# Microcontroller.net
KiCad netlist of a schematic drawn in Altium Designer
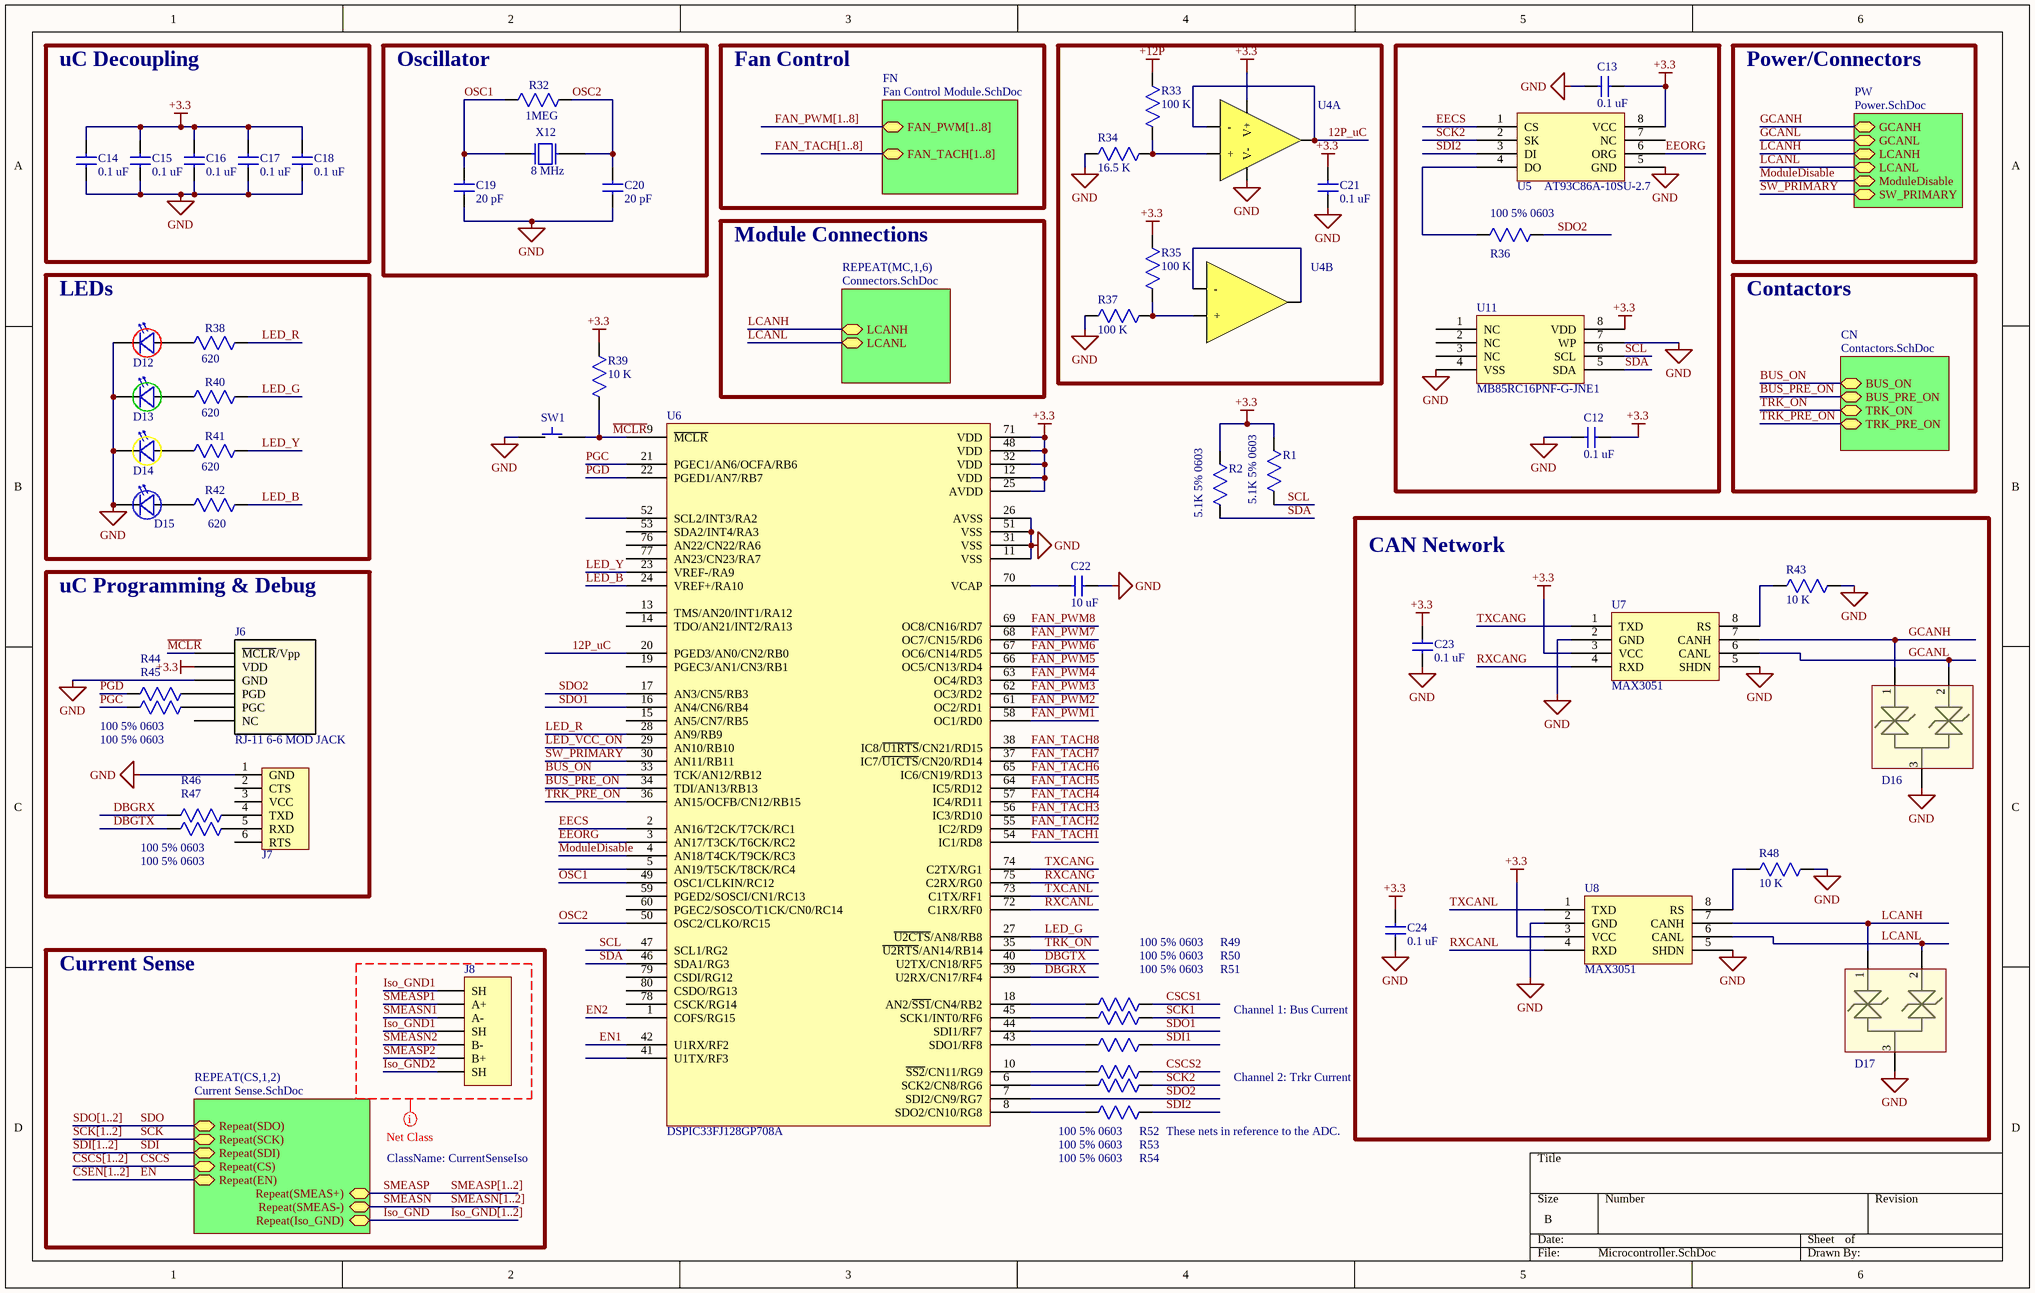
[diagram p0: Microcontroller.SchDoc]

(export (version "E")
  (design (tool "Eeschema 10.0.6"))
  (components
    (comp (ref "C12")
      (value "0.1 uF")
      (footprint "0603_cap")
      (description "CAP CERM 0603")
      (fields (field (name "Comment") "CAP 0603"))
      (libsource (lib "Nutz") (part "C_0603"))
    )
    (comp (ref "C13")
      (value "0.1 uF")
      (footprint "0603_cap")
      (description "CAP CERM 0603")
      (fields (field (name "Comment") "CAP 0603"))
      (libsource (lib "Nutz") (part "C_0603"))
    )
    (comp (ref "C14")
      (value "0.1 uF")
      (footprint "0603_cap")
      (description "CAP CERM 0603")
      (fields (field (name "Comment") "CAP 0603"))
      (libsource (lib "Nutz") (part "C_0603"))
    )
    (comp (ref "C15")
      (value "0.1 uF")
      (footprint "0603_cap")
      (description "CAP CERM 0603")
      (fields (field (name "Comment") "CAP 0603"))
      (libsource (lib "Nutz") (part "C_0603"))
    )
    (comp (ref "C16")
      (value "0.1 uF")
      (footprint "0603_cap")
      (description "CAP CERM 0603")
      (fields (field (name "Comment") "CAP 0603"))
      (libsource (lib "Nutz") (part "C_0603"))
    )
    (comp (ref "C17")
      (value "0.1 uF")
      (footprint "0603_cap")
      (description "CAP CERM 0603")
      (fields (field (name "Comment") "CAP 0603"))
      (libsource (lib "Nutz") (part "C_0603"))
    )
    (comp (ref "C18")
      (value "0.1 uF")
      (footprint "0603_cap")
      (description "CAP CERM 0603")
      (fields (field (name "Comment") "CAP 0603"))
      (libsource (lib "Nutz") (part "C_0603"))
    )
    (comp (ref "C19")
      (value "20 pF")
      (footprint "0805_Capacitor")
      (description "CAP CERM 20PF 5% 100V NP0 0805")
      (fields
        (field (name "MANUFACTURER") "AVX")
        (field (name "Comment") "CAP 20PF")
        (field (name "SVP CREATOR") "Jonathan Nutzmann")
      )
      (libsource (lib "c3_SchLib") (part "C_0805_20PF_100V_5%"))
    )
    (comp (ref "C20")
      (value "20 pF")
      (footprint "0805_Capacitor")
      (description "CAP CERM 20PF 5% 100V NP0 0805")
      (fields
        (field (name "MANUFACTURER") "AVX")
        (field (name "Comment") "CAP 20PF")
        (field (name "SVP CREATOR") "Jonathan Nutzmann")
      )
      (libsource (lib "c3_SchLib") (part "C_0805_20PF_100V_5%"))
    )
    (comp (ref "C21")
      (value "0.1 uF")
      (footprint "0603_cap")
      (description "CAP CERM 0603")
      (fields (field (name "Comment") "CAP 0603"))
      (libsource (lib "Nutz") (part "C_0603"))
    )
    (comp (ref "C22")
      (value "10 uF")
      (footprint "0805_Capacitor")
      (description "CAP CERM 10 uF")
      (fields (field (name "Comment") "CAP 10 uF"))
      (libsource (lib "c3_SchLib") (part "C_0805_10uF"))
    )
    (comp (ref "C23")
      (value "0.1 uF")
      (footprint "0603_cap")
      (description "CAP CERM 0603")
      (fields (field (name "Comment") "CAP 0603"))
      (libsource (lib "Nutz") (part "C_0603"))
    )
    (comp (ref "C24")
      (value "0.1 uF")
      (footprint "0603_cap")
      (description "CAP CERM 0603")
      (fields (field (name "Comment") "CAP 0603"))
      (libsource (lib "Nutz") (part "C_0603"))
    )
    (comp (ref "D12")
      (value "D_LED_0805_RED")
      (footprint "0805P_RED")
      (description "LED CHIPLED 645NM RED DIFF 0805")
      (fields (field (name "SVP CREATOR") "Jonathan Nutzmann"))
      (libsource (lib "c3_SchLib") (part "D_LED_0805_RED"))
    )
    (comp (ref "D13")
      (value "D_LED_0805_GREEN")
      (footprint "0805P_Green")
      (description "LED CHIPLED 570NM GREEN 0805 SMD")
      (fields
        (field (name "MANUFACTURER") "Osram Opto Semiconductors Inc")
        (field (name "SVP CREATOR") "Nate Bolyard")
        (field (name "SVP REVIEWER 1") "Trevtron")
      )
      (libsource (lib "c3_SchLib") (part "D_LED_0805_GREEN"))
    )
    (comp (ref "D14")
      (value "D_LED_0805_YELLOW")
      (footprint "0805P_YELLOW")
      (description "LED 595NM AMBER DIFF SMD 0805")
      (fields (field (name "SVP CREATOR") "Jonathan Nutzmann"))
      (libsource (lib "c3_SchLib") (part "D_LED_0805_YELLOW"))
    )
    (comp (ref "D15")
      (value "D_LED_0805_BLUE")
      (footprint "0805_BLUE")
      (description "LED 2X1.2MM 470NM BL WTR CLR SMD")
      (fields (field (name "SVP CREATOR") "Jonathan Nutzmann"))
      (libsource (lib "c3_SchLib") (part "D_LED_0805_BLUE"))
    )
    (comp (ref "D16")
      (value "CAN TVS")
      (footprint "SOT-23")
      (description "IC CAN BUS PROTECTOR DUAL SOT23")
      (fields (field (name "MANUFACTURER") "ON Semiconductor") (field (name "SVP CREATOR") "Thomas Daede"))
      (libsource (lib "c3_SchLib") (part "D_NUP2105"))
    )
    (comp (ref "D17")
      (value "CAN TVS")
      (footprint "SOT-23")
      (description "IC CAN BUS PROTECTOR DUAL SOT23")
      (fields (field (name "MANUFACTURER") "ON Semiconductor") (field (name "SVP CREATOR") "Thomas Daede"))
      (libsource (lib "c3_SchLib") (part "D_NUP2105"))
    )
    (comp (ref "J6")
      (value "RJ-11 6-6 MOD JACK")
      (footprint "SS-6466-NF")
      (description "SCS RJ-11 Jack")
      (libsource (lib "c3_SchLib") (part "J_ICD PROG"))
    )
    (comp (ref "J7")
      (value "IDC Connector")
      (footprint "6PIN_1_.100IN")
      (description "FTDI Cable VCC I/O")
      (fields (field (name "SVP CREATOR") "Jonathan Nutzmann"))
      (libsource (lib "c3_SchLib") (part "JP_FTDI_USB"))
    )
    (comp (ref "J8")
      (value "J_SATA_0471554001")
      (footprint "SATA_67800-8005")
      (description "CONN SATA HDR 7POS PCB VERT")
      (fields (field (name "MANUFACTURER") "Molex"))
      (libsource (lib "c3_SchLib") (part "J_SATA_0471554001"))
    )
    (comp (ref "R1")
      (value "5.1K 5% 0603")
      (footprint "0603_res")
      (description "RES 0603")
      (libsource (lib "Nutz") (part "R_0603"))
    )
    (comp (ref "R2")
      (value "5.1K 5% 0603")
      (footprint "0603_res")
      (description "RES 0603")
      (libsource (lib "Nutz") (part "R_0603"))
    )
    (comp (ref "R32")
      (value "1MEG")
      (footprint "0805_Resistor")
      (description "RES 1MEG OHM 1/8W 1% 0805 SMD")
      (fields (field (name "Comment") "R_0805_1MEG_1%") (field (name "SVP CREATOR") "Brett Paulsen"))
      (libsource (lib "c3_SchLib") (part "R_0805_1MEG_1%"))
    )
    (comp (ref "R33")
      (value "100 K")
      (footprint "0603_res")
      (description "RES 0603")
      (libsource (lib "Nutz") (part "R_0603"))
    )
    (comp (ref "R34")
      (value "16.5 K")
      (footprint "0603_res")
      (description "RES 0603")
      (libsource (lib "Nutz") (part "R_0603"))
    )
    (comp (ref "R35")
      (value "100 K")
      (footprint "0603_res")
      (description "RES 0603")
      (libsource (lib "Nutz") (part "R_0603"))
    )
    (comp (ref "R36")
      (value "100 5% 0603")
      (footprint "0603_res")
      (description "RES 0603")
      (libsource (lib "Nutz") (part "R_0603"))
    )
    (comp (ref "R37")
      (value "100 K")
      (footprint "0603_res")
      (description "RES 0603")
      (libsource (lib "Nutz") (part "R_0603"))
    )
    (comp (ref "R38")
      (value "620")
      (footprint "0805_Resistor")
      (description "RES 620 OHM 1/8W 1% 0805 SMD")
      (fields (field (name "Comment") "R_0805_620_1%") (field (name "SVP CREATOR") "Jonathan Nutzmann"))
      (libsource (lib "c3_SchLib") (part "R_0805_620_1%"))
    )
    (comp (ref "R39")
      (value "10 K")
      (footprint "0603_res")
      (description "RES 0603")
      (libsource (lib "Nutz") (part "R_0603"))
    )
    (comp (ref "R40")
      (value "620")
      (footprint "0805_Resistor")
      (description "RES 620 OHM 1/8W 1% 0805 SMD")
      (fields (field (name "Comment") "R_0805_620_1%") (field (name "SVP CREATOR") "Jonathan Nutzmann"))
      (libsource (lib "c3_SchLib") (part "R_0805_620_1%"))
    )
    (comp (ref "R41")
      (value "620")
      (footprint "0805_Resistor")
      (description "RES 620 OHM 1/8W 1% 0805 SMD")
      (fields (field (name "Comment") "R_0805_620_1%") (field (name "SVP CREATOR") "Jonathan Nutzmann"))
      (libsource (lib "c3_SchLib") (part "R_0805_620_1%"))
    )
    (comp (ref "R42")
      (value "620")
      (footprint "0805_Resistor")
      (description "RES 620 OHM 1/8W 1% 0805 SMD")
      (fields (field (name "Comment") "R_0805_620_1%") (field (name "SVP CREATOR") "Jonathan Nutzmann"))
      (libsource (lib "c3_SchLib") (part "R_0805_620_1%"))
    )
    (comp (ref "R43")
      (value "10 K")
      (footprint "0603_res")
      (description "RES 0603")
      (libsource (lib "Nutz") (part "R_0603"))
    )
    (comp (ref "R44")
      (value "100 5% 0603")
      (footprint "0603_res")
      (description "RES 0603")
      (libsource (lib "Nutz") (part "R_0603"))
    )
    (comp (ref "R45")
      (value "100 5% 0603")
      (footprint "0603_res")
      (description "RES 0603")
      (libsource (lib "Nutz") (part "R_0603"))
    )
    (comp (ref "R46")
      (value "100 5% 0603")
      (footprint "0603_res")
      (description "RES 0603")
      (libsource (lib "Nutz") (part "R_0603"))
    )
    (comp (ref "R47")
      (value "100 5% 0603")
      (footprint "0603_res")
      (description "RES 0603")
      (libsource (lib "Nutz") (part "R_0603"))
    )
    (comp (ref "R48")
      (value "10 K")
      (footprint "0603_res")
      (description "RES 0603")
      (libsource (lib "Nutz") (part "R_0603"))
    )
    (comp (ref "R49")
      (value "100 5% 0603")
      (footprint "0603_res")
      (description "RES 0603")
      (libsource (lib "Nutz") (part "R_0603"))
    )
    (comp (ref "R50")
      (value "100 5% 0603")
      (footprint "0603_res")
      (description "RES 0603")
      (libsource (lib "Nutz") (part "R_0603"))
    )
    (comp (ref "R51")
      (value "100 5% 0603")
      (footprint "0603_res")
      (description "RES 0603")
      (libsource (lib "Nutz") (part "R_0603"))
    )
    (comp (ref "R52")
      (value "100 5% 0603")
      (footprint "0603_res")
      (description "RES 0603")
      (libsource (lib "Nutz") (part "R_0603"))
    )
    (comp (ref "R53")
      (value "100 5% 0603")
      (footprint "0603_res")
      (description "RES 0603")
      (libsource (lib "Nutz") (part "R_0603"))
    )
    (comp (ref "R54")
      (value "100 5% 0603")
      (footprint "0603_res")
      (description "RES 0603")
      (libsource (lib "Nutz") (part "R_0603"))
    )
    (comp (ref "SW1")
      (value "SW_TACT_SWITCH_6x6")
      (footprint "TACT_SWITCH_6x6")
      (description "SWITCH TACT 6MM BLACK 160GF")
      (fields (field (name "MANUFACTURER") "Tyco Electronics") (field (name "SVP CREATOR") "Nate Bolyard"))
      (libsource (lib "c3_SchLib") (part "SW_TACT_SWITCH_6x6"))
    )
    (comp (ref "U4")
      (value "IC OP AMP")
      (footprint "SOIC127P600X175-8N")
      (description "IC OPAMP 1UA 1.4V DUAL R-R 8SOIC")
      (fields (field (name "MANUFACTURER") "Microchip") (field (name "SVP CREATOR") "Jonathan Nutzmann"))
      (libsource (lib "c3_SchLib") (part "U_MCP6042T-I/SN"))
    )
    (comp (ref "U5")
      (value "AT93C86A-10SU-2.7")
      (footprint "SOIC127P600X175-8N")
      (description "IC EEPROM 16KBIT 2MHZ 8SOIC")
      (fields (field (name "MANUFACTURER") "Atmel") (field (name "MANUFACTURER PN") "AT93C86A-10SU-2.7"))
      (libsource (lib "c3_SchLib") (part "U_AT93C86A-10SU-2.7"))
    )
    (comp (ref "U6")
      (value "DSPIC33FJ128GP708A")
      (footprint "dspic33-tqfp80")
      (description "IC DSPIC MCU/DSP 128K 80-TQFP")
      (fields (field (name "MANUFACTURER") "Microchip") (field (name "SVP CREATOR") "Jonathan Nutzmann"))
      (libsource (lib "c3_SchLib") (part "U_DSPIC33FJ128GP708A"))
    )
    (comp (ref "U7")
      (value "MAX3051")
      (footprint "SOIC127P600X175-8N")
      (description "IC TXRX CAN 1MBPS 8-SOIC 3.3V")
      (fields
        (field (name "MANUFACTURER") "Maxim")
        (field (name "Comment") "U_MAX3051")
        (field (name "SVP CREATOR") "Jonathan Nutzmann")
      )
      (libsource (lib "c3_SchLib") (part "U_MAX3051"))
    )
    (comp (ref "U8")
      (value "MAX3051")
      (footprint "SOIC127P600X175-8N")
      (description "IC TXRX CAN 1MBPS 8-SOIC 3.3V")
      (fields
        (field (name "MANUFACTURER") "Maxim")
        (field (name "Comment") "U_MAX3051")
        (field (name "SVP CREATOR") "Jonathan Nutzmann")
      )
      (libsource (lib "c3_SchLib") (part "U_MAX3051"))
    )
    (comp (ref "U11")
      (value "U_MB85RC16PNF-G-JNE1")
      (footprint "SOIC127P600X175-8N")
      (description "IC FRAM 16KBIT 1MHZ 8SOP")
      (fields
        (field (name "MANUFACTURER") "Fujitsu Semiconductor America Inc")
        (field (name "MANUFACTURER PN") "MB85RC16PNF-G-JNE1")
      )
      (libsource (lib "c3_SchLib") (part "U_MB85RC16PNF-G-JNE1"))
    )
    (comp (ref "X12")
      (value "8 MHz")
      (footprint "HC-49")
      (description "CRYSTAL 8.00 MHZ 20PF 49US")
      (fields
        (field (name "MANUFACTURER") "ECS")
        (field (name "Comment") "HC49")
        (field (name "SVP CREATOR") "Jonathan Nutzmann")
      )
      (libsource (lib "c3_SchLib") (part "X_HC49"))
    )
  )
  (nets
    (net (code "3") (name "+3.3") (class "Default")
      (node (ref "C12") (pin "2") (pinfunction "2_2") (pintype "passive"))
      (node (ref "C13") (pin "2") (pinfunction "2_2") (pintype "passive"))
      (node (ref "C14") (pin "1") (pinfunction "1_1") (pintype "passive"))
      (node (ref "C15") (pin "1") (pinfunction "1_1") (pintype "passive"))
      (node (ref "C16") (pin "1") (pinfunction "1_1") (pintype "passive"))
      (node (ref "C17") (pin "1") (pinfunction "1_1") (pintype "passive"))
      (node (ref "C18") (pin "1") (pinfunction "1_1") (pintype "passive"))
      (node (ref "C21") (pin "1") (pinfunction "1_1") (pintype "passive"))
      (node (ref "C23") (pin "1") (pinfunction "1_1") (pintype "passive"))
      (node (ref "C24") (pin "1") (pinfunction "1_1") (pintype "passive"))
      (node (ref "J6") (pin "2") (pinfunction "VDD_2") (pintype "passive"))
      (node (ref "R1") (pin "1") (pinfunction "1_1") (pintype "passive"))
      (node (ref "R2") (pin "1") (pinfunction "1_1") (pintype "passive"))
      (node (ref "R35") (pin "1") (pinfunction "1_1") (pintype "passive"))
      (node (ref "R39") (pin "1") (pinfunction "1_1") (pintype "passive"))
      (node (ref "U11") (pin "8") (pinfunction "VDD_8") (pintype "passive"))
      (node (ref "U4") (pin "8") (pinfunction "V+_8") (pintype "passive"))
      (node (ref "U5") (pin "8") (pinfunction "VCC_8") (pintype "passive"))
      (node (ref "U6") (pin "12") (pinfunction "VDD_12") (pintype "passive"))
      (node (ref "U6") (pin "25") (pinfunction "AVDD_25") (pintype "passive"))
      (node (ref "U6") (pin "32") (pinfunction "VDD_32") (pintype "passive"))
      (node (ref "U6") (pin "48") (pinfunction "VDD_48") (pintype "passive"))
      (node (ref "U6") (pin "71") (pinfunction "VDD_71") (pintype "passive"))
      (node (ref "U7") (pin "3") (pinfunction "VCC_3") (pintype "passive"))
      (node (ref "U8") (pin "3") (pinfunction "VCC_3") (pintype "passive"))
    )
    (net (code "4") (name "+12P") (class "Default")
      (node (ref "R33") (pin "1") (pinfunction "1_1") (pintype "passive"))
    )
    (net (code "5") (name "/12P_uC") (class "Default")
      (node (ref "U4") (pin "1") (pinfunction "Vo_1") (pintype "passive"))
      (node (ref "U4") (pin "2") (pinfunction "-_2") (pintype "passive"))
      (node (ref "U6") (pin "20") (pinfunction "PGED3/AN0/CN2/RB0_20") (pintype "passive"))
    )
    (net (code "6") (name "/BUS_ON") (class "Default")
      (node (ref "U6") (pin "33") (pinfunction "TCK/AN12/RB12_33") (pintype "passive"))
    )
    (net (code "7") (name "/BUS_PRE_ON") (class "Default")
      (node (ref "U6") (pin "34") (pinfunction "TDI/AN13/RB13_34") (pintype "passive"))
    )
    (net (code "9") (name "/CSCS1") (class "Default")
      (node (ref "R51") (pin "1") (pinfunction "1_1") (pintype "passive"))
    )
    (net (code "10") (name "/CSCS2") (class "Default")
      (node (ref "R54") (pin "1") (pinfunction "1_1") (pintype "passive"))
    )
    (net (code "13") (name "/DBGRX") (class "Default")
      (node (ref "R46") (pin "2") (pinfunction "2_2") (pintype "passive"))
      (node (ref "U6") (pin "39") (pinfunction "U2RX/CN17/RF4_39") (pintype "passive"))
    )
    (net (code "14") (name "/DBGTX") (class "Default")
      (node (ref "R47") (pin "2") (pinfunction "2_2") (pintype "passive"))
      (node (ref "U6") (pin "40") (pinfunction "U2TX/CN18/RF5_40") (pintype "passive"))
    )
    (net (code "15") (name "/EECS") (class "Default")
      (node (ref "U5") (pin "1") (pinfunction "CS_1") (pintype "passive"))
      (node (ref "U6") (pin "2") (pinfunction "AN16/T2CK/T7CK/RC1_2") (pintype "passive"))
    )
    (net (code "16") (name "/EEORG") (class "Default")
      (node (ref "U5") (pin "6") (pinfunction "ORG_6") (pintype "passive"))
      (node (ref "U6") (pin "3") (pinfunction "AN17/T3CK/T6CK/RC2_3") (pintype "passive"))
    )
    (net (code "18") (name "/EN1") (class "Default")
      (node (ref "U6") (pin "42") (pinfunction "U1RX/RF2_42") (pintype "passive"))
    )
    (net (code "19") (name "/EN2") (class "Default")
      (node (ref "U6") (pin "1") (pinfunction "COFS/RG15_1") (pintype "passive"))
    )
    (net (code "20") (name "/FAN_PWM1") (class "Default")
      (node (ref "U6") (pin "58") (pinfunction "OC1/RD0_58") (pintype "passive"))
    )
    (net (code "21") (name "/FAN_PWM2") (class "Default")
      (node (ref "U6") (pin "61") (pinfunction "OC2/RD1_61") (pintype "passive"))
    )
    (net (code "22") (name "/FAN_PWM3") (class "Default")
      (node (ref "U6") (pin "62") (pinfunction "OC3/RD2_62") (pintype "passive"))
    )
    (net (code "23") (name "/FAN_PWM4") (class "Default")
      (node (ref "U6") (pin "63") (pinfunction "OC4/RD3_63") (pintype "passive"))
    )
    (net (code "24") (name "/FAN_PWM5") (class "Default")
      (node (ref "U6") (pin "66") (pinfunction "OC5/CN13/RD4_66") (pintype "passive"))
    )
    (net (code "25") (name "/FAN_PWM6") (class "Default")
      (node (ref "U6") (pin "67") (pinfunction "OC6/CN14/RD5_67") (pintype "passive"))
    )
    (net (code "26") (name "/FAN_PWM7") (class "Default")
      (node (ref "U6") (pin "68") (pinfunction "OC7/CN15/RD6_68") (pintype "passive"))
    )
    (net (code "27") (name "/FAN_PWM8") (class "Default")
      (node (ref "U6") (pin "69") (pinfunction "OC8/CN16/RD7_69") (pintype "passive"))
    )
    (net (code "29") (name "/FAN_TACH1") (class "Default")
      (node (ref "U6") (pin "54") (pinfunction "IC1/RD8_54") (pintype "passive"))
    )
    (net (code "30") (name "/FAN_TACH2") (class "Default")
      (node (ref "U6") (pin "55") (pinfunction "IC2/RD9_55") (pintype "passive"))
    )
    (net (code "31") (name "/FAN_TACH3") (class "Default")
      (node (ref "U6") (pin "56") (pinfunction "IC3/RD10_56") (pintype "passive"))
    )
    (net (code "32") (name "/FAN_TACH4") (class "Default")
      (node (ref "U6") (pin "57") (pinfunction "IC4/RD11_57") (pintype "passive"))
    )
    (net (code "33") (name "/FAN_TACH5") (class "Default")
      (node (ref "U6") (pin "64") (pinfunction "IC5/RD12_64") (pintype "passive"))
    )
    (net (code "34") (name "/FAN_TACH6") (class "Default")
      (node (ref "U6") (pin "65") (pinfunction "IC6/CN19/RD13_65") (pintype "passive"))
    )
    (net (code "35") (name "/FAN_TACH7") (class "Default")
      (node (ref "U6") (pin "37") (pinfunction "IC7/~{U1CTS}/CN20/RD14_37") (pintype "passive"))
    )
    (net (code "36") (name "/FAN_TACH8") (class "Default")
      (node (ref "U6") (pin "38") (pinfunction "IC8/~{U1RTS}/CN21/RD15_38") (pintype "passive"))
    )
    (net (code "38") (name "/GCANH") (class "Default")
      (node (ref "D16") (pin "1") (pintype "passive"))
      (node (ref "U7") (pin "7") (pinfunction "CANH_7") (pintype "passive"))
    )
    (net (code "39") (name "/GCANL") (class "Default")
      (node (ref "D16") (pin "2") (pintype "passive"))
      (node (ref "U7") (pin "6") (pinfunction "CANL_6") (pintype "passive"))
    )
    (net (code "41") (name "/Iso_GND1") (class "Default")
      (node (ref "J8") (pin "1") (pinfunction "SH_1") (pintype "passive"))
      (node (ref "J8") (pin "4") (pinfunction "SH_4") (pintype "passive"))
    )
    (net (code "42") (name "/Iso_GND2") (class "Default")
      (node (ref "J8") (pin "7") (pinfunction "SH_7") (pintype "passive"))
    )
    (net (code "44") (name "/LCANH") (class "Default")
      (node (ref "D17") (pin "1") (pintype "passive"))
      (node (ref "U8") (pin "7") (pinfunction "CANH_7") (pintype "passive"))
    )
    (net (code "45") (name "/LCANL") (class "Default")
      (node (ref "D17") (pin "2") (pintype "passive"))
      (node (ref "U8") (pin "6") (pinfunction "CANL_6") (pintype "passive"))
    )
    (net (code "46") (name "/LED_B") (class "Default")
      (node (ref "R42") (pin "1") (pinfunction "1_1") (pintype "passive"))
      (node (ref "U6") (pin "24") (pinfunction "VREF+/RA10_24") (pintype "passive"))
    )
    (net (code "47") (name "/LED_G") (class "Default")
      (node (ref "R40") (pin "1") (pinfunction "1_1") (pintype "passive"))
      (node (ref "U6") (pin "27") (pinfunction "~{U2CTS}/AN8/RB8_27") (pintype "passive"))
    )
    (net (code "48") (name "/LED_R") (class "Default")
      (node (ref "R38") (pin "1") (pinfunction "1_1") (pintype "passive"))
      (node (ref "U6") (pin "28") (pinfunction "AN9/RB9_28") (pintype "passive"))
    )
    (net (code "49") (name "/LED_VCC_ON") (class "Default")
      (node (ref "U6") (pin "29") (pinfunction "AN10/RB10_29") (pintype "passive"))
    )
    (net (code "50") (name "/LED_Y") (class "Default")
      (node (ref "R41") (pin "1") (pinfunction "1_1") (pintype "passive"))
      (node (ref "U6") (pin "23") (pinfunction "VREF-/RA9_23") (pintype "passive"))
    )
    (net (code "51") (name "/ModuleDisable") (class "Default")
      (node (ref "U6") (pin "4") (pinfunction "AN18/T4CK/T9CK/RC3_4") (pintype "passive"))
    )
    (net (code "52") (name "/OSC1") (class "Default")
      (node (ref "C19") (pin "1") (pinfunction "1_1") (pintype "passive"))
      (node (ref "R32") (pin "2") (pinfunction "2_2") (pintype "passive"))
      (node (ref "U6") (pin "49") (pinfunction "OSC1/CLKIN/RC12_49") (pintype "passive"))
      (node (ref "X12") (pin "2") (pinfunction "2_2") (pintype "passive"))
    )
    (net (code "53") (name "/OSC2") (class "Default")
      (node (ref "C20") (pin "1") (pinfunction "1_1") (pintype "passive"))
      (node (ref "R32") (pin "1") (pinfunction "1_1") (pintype "passive"))
      (node (ref "U6") (pin "50") (pinfunction "OSC2/CLKO/RC15_50") (pintype "passive"))
      (node (ref "X12") (pin "1") (pinfunction "1_1") (pintype "passive"))
    )
    (net (code "54") (name "/PGC") (class "Default")
      (node (ref "R45") (pin "2") (pinfunction "2_2") (pintype "passive"))
      (node (ref "U6") (pin "21") (pinfunction "PGEC1/AN6/OCFA/RB6_21") (pintype "passive"))
    )
    (net (code "55") (name "/PGD") (class "Default")
      (node (ref "R44") (pin "2") (pinfunction "2_2") (pintype "passive"))
      (node (ref "U6") (pin "22") (pinfunction "PGED1/AN7/RB7_22") (pintype "passive"))
    )
    (net (code "56") (name "/RXCANG") (class "Default")
      (node (ref "U6") (pin "75") (pinfunction "C2RX/RG0_75") (pintype "passive"))
      (node (ref "U7") (pin "4") (pinfunction "RXD_4") (pintype "passive"))
    )
    (net (code "57") (name "/RXCANL") (class "Default")
      (node (ref "U6") (pin "72") (pinfunction "C1RX/RF0_72") (pintype "passive"))
      (node (ref "U8") (pin "4") (pinfunction "RXD_4") (pintype "passive"))
    )
    (net (code "59") (name "/SCK1") (class "Default")
      (node (ref "R50") (pin "1") (pinfunction "1_1") (pintype "passive"))
    )
    (net (code "60") (name "/SCK2") (class "Default")
      (node (ref "R53") (pin "1") (pinfunction "1_1") (pintype "passive"))
      (node (ref "U5") (pin "2") (pinfunction "SK_2") (pintype "passive"))
    )
    (net (code "62") (name "/SCL") (class "Default")
      (node (ref "R1") (pin "2") (pinfunction "2_2") (pintype "passive"))
      (node (ref "U11") (pin "6") (pinfunction "SCL_6") (pintype "passive"))
      (node (ref "U6") (pin "47") (pinfunction "SCL1/RG2_47") (pintype "passive"))
    )
    (net (code "63") (name "/SDA") (class "Default")
      (node (ref "R2") (pin "2") (pinfunction "2_2") (pintype "passive"))
      (node (ref "U11") (pin "5") (pinfunction "SDA_5") (pintype "passive"))
      (node (ref "U6") (pin "46") (pinfunction "SDA1/RG3_46") (pintype "passive"))
    )
    (net (code "65") (name "/SDI1") (class "Default")
      (node (ref "R49") (pin "1") (pinfunction "1_1") (pintype "passive"))
    )
    (net (code "66") (name "/SDI2") (class "Default")
      (node (ref "R52") (pin "1") (pinfunction "1_1") (pintype "passive"))
      (node (ref "U5") (pin "3") (pinfunction "DI_3") (pintype "passive"))
    )
    (net (code "69") (name "/SDO1") (class "Default")
      (node (ref "U6") (pin "16") (pinfunction "AN4/CN6/RB4_16") (pintype "passive"))
      (node (ref "U6") (pin "44") (pinfunction "SDI1/RF7_44") (pintype "passive"))
    )
    (net (code "70") (name "/SDO2") (class "Default")
      (node (ref "R36") (pin "1") (pinfunction "1_1") (pintype "passive"))
      (node (ref "U6") (pin "17") (pinfunction "AN3/CN5/RB3_17") (pintype "passive"))
      (node (ref "U6") (pin "7") (pinfunction "SDI2/CN9/RG7_7") (pintype "passive"))
    )
    (net (code "73") (name "/SMEASN1") (class "Default")
      (node (ref "J8") (pin "3") (pinfunction "A-_3") (pintype "passive"))
    )
    (net (code "74") (name "/SMEASN2") (class "Default")
      (node (ref "J8") (pin "5") (pinfunction "B-_5") (pintype "passive"))
    )
    (net (code "77") (name "/SMEASP1") (class "Default")
      (node (ref "J8") (pin "2") (pinfunction "A+_2") (pintype "passive"))
    )
    (net (code "78") (name "/SMEASP2") (class "Default")
      (node (ref "J8") (pin "6") (pinfunction "B+_6") (pintype "passive"))
    )
    (net (code "80") (name "/SW_PRIMARY") (class "Default")
      (node (ref "U6") (pin "30") (pinfunction "AN11/RB11_30") (pintype "passive"))
    )
    (net (code "81") (name "/TRK_ON") (class "Default")
      (node (ref "U6") (pin "35") (pinfunction "~{U2RTS}/AN14/RB14_35") (pintype "passive"))
    )
    (net (code "82") (name "/TRK_PRE_ON") (class "Default")
      (node (ref "U6") (pin "36") (pinfunction "AN15/OCFB/CN12/RB15_36") (pintype "passive"))
    )
    (net (code "83") (name "/TXCANG") (class "Default")
      (node (ref "U6") (pin "74") (pinfunction "C2TX/RG1_74") (pintype "passive"))
      (node (ref "U7") (pin "1") (pinfunction "TXD_1") (pintype "passive"))
    )
    (net (code "84") (name "/TXCANL") (class "Default")
      (node (ref "U6") (pin "73") (pinfunction "C1TX/RF1_73") (pintype "passive"))
      (node (ref "U8") (pin "1") (pinfunction "TXD_1") (pintype "passive"))
    )
    (net (code "85") (name "/~{MCLR}") (class "Default")
      (node (ref "J6") (pin "1") (pinfunction "~{MCLR}/Vpp_1") (pintype "passive"))
      (node (ref "R39") (pin "2") (pinfunction "2_2") (pintype "passive"))
      (node (ref "SW1") (pin "2") (pinfunction "2_2") (pintype "passive"))
      (node (ref "U6") (pin "9") (pinfunction "~{MCLR}_9") (pintype "passive"))
    )
    (net (code "86") (name "GND") (class "Default")
      (node (ref "C12") (pin "1") (pinfunction "1_1") (pintype "passive"))
      (node (ref "C13") (pin "1") (pinfunction "1_1") (pintype "passive"))
      (node (ref "C14") (pin "2") (pinfunction "2_2") (pintype "passive"))
      (node (ref "C15") (pin "2") (pinfunction "2_2") (pintype "passive"))
      (node (ref "C16") (pin "2") (pinfunction "2_2") (pintype "passive"))
      (node (ref "C17") (pin "2") (pinfunction "2_2") (pintype "passive"))
      (node (ref "C18") (pin "2") (pinfunction "2_2") (pintype "passive"))
      (node (ref "C19") (pin "2") (pinfunction "2_2") (pintype "passive"))
      (node (ref "C20") (pin "2") (pinfunction "2_2") (pintype "passive"))
      (node (ref "C21") (pin "2") (pinfunction "2_2") (pintype "passive"))
      (node (ref "C22") (pin "1") (pinfunction "1_1") (pintype "passive"))
      (node (ref "C23") (pin "2") (pinfunction "2_2") (pintype "passive"))
      (node (ref "C24") (pin "2") (pinfunction "2_2") (pintype "passive"))
      (node (ref "D12") (pin "1") (pinfunction "Cathode_1") (pintype "passive"))
      (node (ref "D13") (pin "1") (pinfunction "Cathode_1") (pintype "passive"))
      (node (ref "D14") (pin "1") (pinfunction "Cathode_1") (pintype "passive"))
      (node (ref "D15") (pin "1") (pinfunction "Cathode_1") (pintype "passive"))
      (node (ref "D16") (pin "3") (pintype "passive"))
      (node (ref "D17") (pin "3") (pintype "passive"))
      (node (ref "J6") (pin "3") (pinfunction "GND_3") (pintype "passive"))
      (node (ref "J7") (pin "1") (pinfunction "GND_1") (pintype "passive"))
      (node (ref "R34") (pin "1") (pinfunction "1_1") (pintype "passive"))
      (node (ref "R37") (pin "1") (pinfunction "1_1") (pintype "passive"))
      (node (ref "R43") (pin "1") (pinfunction "1_1") (pintype "passive"))
      (node (ref "R48") (pin "1") (pinfunction "1_1") (pintype "passive"))
      (node (ref "SW1") (pin "1") (pinfunction "1_1") (pintype "passive"))
      (node (ref "U11") (pin "4") (pinfunction "VSS_4") (pintype "passive"))
      (node (ref "U11") (pin "7") (pinfunction "WP_7") (pintype "passive"))
      (node (ref "U4") (pin "4") (pinfunction "V-_4") (pintype "passive"))
      (node (ref "U5") (pin "5") (pinfunction "GND_5") (pintype "passive"))
      (node (ref "U6") (pin "11") (pinfunction "VSS_11") (pintype "passive"))
      (node (ref "U6") (pin "26") (pinfunction "AVSS_26") (pintype "passive"))
      (node (ref "U6") (pin "31") (pinfunction "VSS_31") (pintype "passive"))
      (node (ref "U6") (pin "51") (pinfunction "VSS_51") (pintype "passive"))
      (node (ref "U7") (pin "2") (pinfunction "GND_2") (pintype "passive"))
      (node (ref "U7") (pin "5") (pinfunction "SHDN_5") (pintype "passive"))
      (node (ref "U8") (pin "2") (pinfunction "GND_2") (pintype "passive"))
      (node (ref "U8") (pin "5") (pinfunction "SHDN_5") (pintype "passive"))
    )
    (net (code "87") (name "Net-(D12-Anode)") (class "Default")
      (node (ref "D12") (pin "2") (pinfunction "Anode_2") (pintype "passive"))
      (node (ref "R38") (pin "2") (pinfunction "2_2") (pintype "passive"))
    )
    (net (code "88") (name "Net-(D13-Anode)") (class "Default")
      (node (ref "D13") (pin "2") (pinfunction "Anode_2") (pintype "passive"))
      (node (ref "R40") (pin "2") (pinfunction "2_2") (pintype "passive"))
    )
    (net (code "89") (name "Net-(D14-Anode)") (class "Default")
      (node (ref "D14") (pin "2") (pinfunction "Anode_2") (pintype "passive"))
      (node (ref "R41") (pin "2") (pinfunction "2_2") (pintype "passive"))
    )
    (net (code "90") (name "Net-(D15-Anode)") (class "Default")
      (node (ref "D15") (pin "2") (pinfunction "Anode_2") (pintype "passive"))
      (node (ref "R42") (pin "2") (pinfunction "2_2") (pintype "passive"))
    )
    (net (code "91") (name "Net-(J6-PGC)") (class "Default")
      (node (ref "J6") (pin "5") (pinfunction "PGC_5") (pintype "passive"))
      (node (ref "R45") (pin "1") (pinfunction "1_1") (pintype "passive"))
    )
    (net (code "92") (name "Net-(J6-PGD)") (class "Default")
      (node (ref "J6") (pin "4") (pinfunction "PGD_4") (pintype "passive"))
      (node (ref "R44") (pin "1") (pinfunction "1_1") (pintype "passive"))
    )
    (net (code "93") (name "Net-(J7-RXD)") (class "Default")
      (node (ref "J7") (pin "5") (pinfunction "RXD_5") (pintype "passive"))
      (node (ref "R47") (pin "1") (pinfunction "1_1") (pintype "passive"))
    )
    (net (code "94") (name "Net-(J7-TXD)") (class "Default")
      (node (ref "J7") (pin "4") (pinfunction "TXD_4") (pintype "passive"))
      (node (ref "R46") (pin "1") (pinfunction "1_1") (pintype "passive"))
    )
    (net (code "95") (name "Net-(U4A-+)") (class "Default")
      (node (ref "R33") (pin "2") (pinfunction "2_2") (pintype "passive"))
      (node (ref "R34") (pin "2") (pinfunction "2_2") (pintype "passive"))
      (node (ref "U4") (pin "3") (pinfunction "+_3") (pintype "passive"))
    )
    (net (code "96") (name "Net-(U4B-+)") (class "Default")
      (node (ref "R35") (pin "2") (pinfunction "2_2") (pintype "passive"))
      (node (ref "R37") (pin "2") (pinfunction "2_2") (pintype "passive"))
      (node (ref "U4") (pin "5") (pinfunction "+_5") (pintype "passive"))
    )
    (net (code "97") (name "Net-(U4B--)") (class "Default")
      (node (ref "U4") (pin "6") (pinfunction "-_6") (pintype "passive"))
      (node (ref "U4") (pin "7") (pinfunction "Vo_7") (pintype "passive"))
    )
    (net (code "98") (name "Net-(U5-DO)") (class "Default")
      (node (ref "R36") (pin "2") (pinfunction "2_2") (pintype "passive"))
      (node (ref "U5") (pin "4") (pinfunction "DO_4") (pintype "passive"))
    )
    (net (code "99") (name "Net-(U6-AN2{slash}~{SS1}{slash}CN4{slash}RB2)") (class "Default")
      (node (ref "R51") (pin "2") (pinfunction "2_2") (pintype "passive"))
      (node (ref "U6") (pin "18") (pinfunction "AN2/~{SS1}/CN4/RB2_18") (pintype "passive"))
    )
    (net (code "100") (name "Net-(U6-SCK1{slash}INT0{slash}RF6)") (class "Default")
      (node (ref "R50") (pin "2") (pinfunction "2_2") (pintype "passive"))
      (node (ref "U6") (pin "45") (pinfunction "SCK1/INT0/RF6_45") (pintype "passive"))
    )
    (net (code "101") (name "Net-(U6-SCK2{slash}CN8{slash}RG6)") (class "Default")
      (node (ref "R53") (pin "2") (pinfunction "2_2") (pintype "passive"))
      (node (ref "U6") (pin "6") (pinfunction "SCK2/CN8/RG6_6") (pintype "passive"))
    )
    (net (code "102") (name "Net-(U6-SDO1{slash}RF8)") (class "Default")
      (node (ref "R49") (pin "2") (pinfunction "2_2") (pintype "passive"))
      (node (ref "U6") (pin "43") (pinfunction "SDO1/RF8_43") (pintype "passive"))
    )
    (net (code "103") (name "Net-(U6-SDO2{slash}CN10{slash}RG8)") (class "Default")
      (node (ref "R52") (pin "2") (pinfunction "2_2") (pintype "passive"))
      (node (ref "U6") (pin "8") (pinfunction "SDO2/CN10/RG8_8") (pintype "passive"))
    )
    (net (code "104") (name "Net-(U6-VCAP)") (class "Default")
      (node (ref "C22") (pin "2") (pinfunction "2_2") (pintype "passive"))
      (node (ref "U6") (pin "70") (pinfunction "VCAP_70") (pintype "passive"))
    )
    (net (code "105") (name "Net-(U6-~{SS2}{slash}CN11{slash}RG9)") (class "Default")
      (node (ref "R54") (pin "2") (pinfunction "2_2") (pintype "passive"))
      (node (ref "U6") (pin "10") (pinfunction "~{SS2}/CN11/RG9_10") (pintype "passive"))
    )
    (net (code "106") (name "Net-(U7-RS)") (class "Default")
      (node (ref "R43") (pin "2") (pinfunction "2_2") (pintype "passive"))
      (node (ref "U7") (pin "8") (pinfunction "RS_8") (pintype "passive"))
    )
    (net (code "107") (name "Net-(U8-RS)") (class "Default")
      (node (ref "R48") (pin "2") (pinfunction "2_2") (pintype "passive"))
      (node (ref "U8") (pin "8") (pinfunction "RS_8") (pintype "passive"))
    )
    (net (code "108") (name "unconnected-(J6-NC-Pad6)") (class "Default")
      (node (ref "J6") (pin "6") (pinfunction "NC_6") (pintype "passive"))
    )
    (net (code "109") (name "unconnected-(J7-CTS-Pad2)") (class "Default")
      (node (ref "J7") (pin "2") (pinfunction "CTS_2") (pintype "passive"))
    )
    (net (code "110") (name "unconnected-(J7-RTS-Pad6)") (class "Default")
      (node (ref "J7") (pin "6") (pinfunction "RTS_6") (pintype "passive"))
    )
    (net (code "111") (name "unconnected-(J7-VCC-Pad3)") (class "Default")
      (node (ref "J7") (pin "3") (pinfunction "VCC_3") (pintype "passive"))
    )
    (net (code "112") (name "unconnected-(U5-NC-Pad7)") (class "Default")
      (node (ref "U5") (pin "7") (pinfunction "NC_7") (pintype "passive"))
    )
    (net (code "113") (name "unconnected-(U6-AN5{slash}CN7{slash}RB5-Pad15)") (class "Default")
      (node (ref "U6") (pin "15") (pinfunction "AN5/CN7/RB5_15") (pintype "passive"))
    )
    (net (code "114") (name "unconnected-(U6-AN19{slash}T5CK{slash}T8CK{slash}RC4-Pad5)") (class "Default")
      (node (ref "U6") (pin "5") (pinfunction "AN19/T5CK/T8CK/RC4_5") (pintype "passive"))
    )
    (net (code "115") (name "unconnected-(U6-AN22{slash}CN22{slash}RA6-Pad76)") (class "Default")
      (node (ref "U6") (pin "76") (pinfunction "AN22/CN22/RA6_76") (pintype "passive"))
    )
    (net (code "116") (name "unconnected-(U6-AN23{slash}CN23{slash}RA7-Pad77)") (class "Default")
      (node (ref "U6") (pin "77") (pinfunction "AN23/CN23/RA7_77") (pintype "passive"))
    )
    (net (code "117") (name "unconnected-(U6-CSCK{slash}RG14-Pad78)") (class "Default")
      (node (ref "U6") (pin "78") (pinfunction "CSCK/RG14_78") (pintype "passive"))
    )
    (net (code "118") (name "unconnected-(U6-CSDI{slash}RG12-Pad79)") (class "Default")
      (node (ref "U6") (pin "79") (pinfunction "CSDI/RG12_79") (pintype "passive"))
    )
    (net (code "119") (name "unconnected-(U6-CSDO{slash}RG13-Pad80)") (class "Default")
      (node (ref "U6") (pin "80") (pinfunction "CSDO/RG13_80") (pintype "passive"))
    )
    (net (code "120") (name "unconnected-(U6-PGEC2{slash}SOSCO{slash}T1CK{slash}CN0{slash}RC14-Pad60)") (class "Default")
      (node (ref "U6") (pin "60") (pinfunction "PGEC2/SOSCO/T1CK/CN0/RC14_60") (pintype "passive"))
    )
    (net (code "121") (name "unconnected-(U6-PGEC3{slash}AN1{slash}CN3{slash}RB1-Pad19)") (class "Default")
      (node (ref "U6") (pin "19") (pinfunction "PGEC3/AN1/CN3/RB1_19") (pintype "passive"))
    )
    (net (code "122") (name "unconnected-(U6-PGED2{slash}SOSCI{slash}CN1{slash}RC13-Pad59)") (class "Default")
      (node (ref "U6") (pin "59") (pinfunction "PGED2/SOSCI/CN1/RC13_59") (pintype "passive"))
    )
    (net (code "123") (name "unconnected-(U6-SCL2{slash}INT3{slash}RA2-Pad52)") (class "Default")
      (node (ref "U6") (pin "52") (pinfunction "SCL2/INT3/RA2_52") (pintype "passive"))
    )
    (net (code "124") (name "unconnected-(U6-SDA2{slash}INT4{slash}RA3-Pad53)") (class "Default")
      (node (ref "U6") (pin "53") (pinfunction "SDA2/INT4/RA3_53") (pintype "passive"))
    )
    (net (code "125") (name "unconnected-(U6-TDO{slash}AN21{slash}INT2{slash}RA13-Pad14)") (class "Default")
      (node (ref "U6") (pin "14") (pinfunction "TDO/AN21/INT2/RA13_14") (pintype "passive"))
    )
    (net (code "126") (name "unconnected-(U6-TMS{slash}AN20{slash}INT1{slash}RA12-Pad13)") (class "Default")
      (node (ref "U6") (pin "13") (pinfunction "TMS/AN20/INT1/RA12_13") (pintype "passive"))
    )
    (net (code "127") (name "unconnected-(U6-U1TX{slash}RF3-Pad41)") (class "Default")
      (node (ref "U6") (pin "41") (pinfunction "U1TX/RF3_41") (pintype "passive"))
    )
    (net (code "128") (name "unconnected-(U11-NC-Pad1)") (class "Default")
      (node (ref "U11") (pin "1") (pinfunction "NC_1") (pintype "passive"))
    )
    (net (code "129") (name "unconnected-(U11-NC-Pad2)") (class "Default")
      (node (ref "U11") (pin "2") (pinfunction "NC_2") (pintype "passive"))
    )
    (net (code "130") (name "unconnected-(U11-NC-Pad3)") (class "Default")
      (node (ref "U11") (pin "3") (pinfunction "NC_3") (pintype "passive"))
    )
  )
)
